# twelite_module.net
KiCad netlist of a schematic drawn in EAGLE
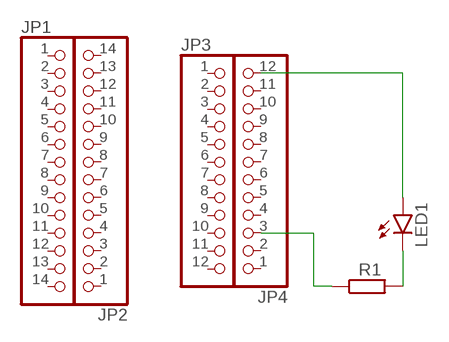
[diagram p0: schematic, sheet 1]

(export (version "E")
  (design (tool "Eeschema 10.0.6"))
  (components
    (comp (ref "JP1")
      (value "PINHD-1X14")
      (footprint "eagle-import:1X14")
      (libsource (lib "eagle-import") (part "PINHD-1X14"))
    )
    (comp (ref "JP2")
      (value "PINHD-1X14")
      (footprint "eagle-import:1X14")
      (libsource (lib "eagle-import") (part "PINHD-1X14"))
    )
    (comp (ref "JP3")
      (value "PINHD-1X12")
      (footprint "eagle-import:1X12")
      (libsource (lib "eagle-import") (part "PINHD-1X12"))
    )
    (comp (ref "JP4")
      (value "PINHD-1X12")
      (footprint "eagle-import:1X12")
      (libsource (lib "eagle-import") (part "PINHD-1X12"))
    )
    (comp (ref "LED1")
      (value "LED5MM")
      (footprint "eagle-import:LED5MM")
      (libsource (lib "eagle-import") (part "LED5MM"))
    )
    (comp (ref "R1")
      (value "R-EU_0204/7")
      (footprint "eagle-import:0204_7")
      (libsource (lib "eagle-import") (part "R-EU_0204/7"))
    )
  )
  (nets
    (net (code "1") (name "Net-(JP4-Pad3)") (class "Default")
      (node (ref "JP4") (pin "3") (pinfunction "3_3") (pintype "passive"))
      (node (ref "R1") (pin "1") (pinfunction "1_1") (pintype "passive"))
    )
    (net (code "2") (name "Net-(JP4-Pad12)") (class "Default")
      (node (ref "JP4") (pin "12") (pinfunction "12_12") (pintype "passive"))
      (node (ref "LED1") (pin "A") (pinfunction "A_A") (pintype "passive"))
    )
    (net (code "3") (name "Net-(LED1-C)") (class "Default")
      (node (ref "LED1") (pin "K") (pinfunction "C_K") (pintype "passive"))
      (node (ref "R1") (pin "2") (pinfunction "2_2") (pintype "passive"))
    )
    (net (code "4") (name "unconnected-(JP1-Pad1)") (class "Default")
      (node (ref "JP1") (pin "1") (pinfunction "1_1") (pintype "passive"))
    )
    (net (code "5") (name "unconnected-(JP1-Pad2)") (class "Default")
      (node (ref "JP1") (pin "2") (pinfunction "2_2") (pintype "passive"))
    )
    (net (code "6") (name "unconnected-(JP1-Pad3)") (class "Default")
      (node (ref "JP1") (pin "3") (pinfunction "3_3") (pintype "passive"))
    )
    (net (code "7") (name "unconnected-(JP1-Pad4)") (class "Default")
      (node (ref "JP1") (pin "4") (pinfunction "4_4") (pintype "passive"))
    )
    (net (code "8") (name "unconnected-(JP1-Pad5)") (class "Default")
      (node (ref "JP1") (pin "5") (pinfunction "5_5") (pintype "passive"))
    )
    (net (code "9") (name "unconnected-(JP1-Pad6)") (class "Default")
      (node (ref "JP1") (pin "6") (pinfunction "6_6") (pintype "passive"))
    )
    (net (code "10") (name "unconnected-(JP1-Pad7)") (class "Default")
      (node (ref "JP1") (pin "7") (pinfunction "7_7") (pintype "passive"))
    )
    (net (code "11") (name "unconnected-(JP1-Pad8)") (class "Default")
      (node (ref "JP1") (pin "8") (pinfunction "8_8") (pintype "passive"))
    )
    (net (code "12") (name "unconnected-(JP1-Pad9)") (class "Default")
      (node (ref "JP1") (pin "9") (pinfunction "9_9") (pintype "passive"))
    )
    (net (code "13") (name "unconnected-(JP1-Pad10)") (class "Default")
      (node (ref "JP1") (pin "10") (pinfunction "10_10") (pintype "passive"))
    )
    (net (code "14") (name "unconnected-(JP1-Pad11)") (class "Default")
      (node (ref "JP1") (pin "11") (pinfunction "11_11") (pintype "passive"))
    )
    (net (code "15") (name "unconnected-(JP1-Pad12)") (class "Default")
      (node (ref "JP1") (pin "12") (pinfunction "12_12") (pintype "passive"))
    )
    (net (code "16") (name "unconnected-(JP1-Pad13)") (class "Default")
      (node (ref "JP1") (pin "13") (pinfunction "13_13") (pintype "passive"))
    )
    (net (code "17") (name "unconnected-(JP1-Pad14)") (class "Default")
      (node (ref "JP1") (pin "14") (pinfunction "14_14") (pintype "passive"))
    )
    (net (code "18") (name "unconnected-(JP2-Pad1)") (class "Default")
      (node (ref "JP2") (pin "1") (pinfunction "1_1") (pintype "passive"))
    )
    (net (code "19") (name "unconnected-(JP2-Pad2)") (class "Default")
      (node (ref "JP2") (pin "2") (pinfunction "2_2") (pintype "passive"))
    )
    (net (code "20") (name "unconnected-(JP2-Pad3)") (class "Default")
      (node (ref "JP2") (pin "3") (pinfunction "3_3") (pintype "passive"))
    )
    (net (code "21") (name "unconnected-(JP2-Pad4)") (class "Default")
      (node (ref "JP2") (pin "4") (pinfunction "4_4") (pintype "passive"))
    )
    (net (code "22") (name "unconnected-(JP2-Pad5)") (class "Default")
      (node (ref "JP2") (pin "5") (pinfunction "5_5") (pintype "passive"))
    )
    (net (code "23") (name "unconnected-(JP2-Pad6)") (class "Default")
      (node (ref "JP2") (pin "6") (pinfunction "6_6") (pintype "passive"))
    )
    (net (code "24") (name "unconnected-(JP2-Pad7)") (class "Default")
      (node (ref "JP2") (pin "7") (pinfunction "7_7") (pintype "passive"))
    )
    (net (code "25") (name "unconnected-(JP2-Pad8)") (class "Default")
      (node (ref "JP2") (pin "8") (pinfunction "8_8") (pintype "passive"))
    )
    (net (code "26") (name "unconnected-(JP2-Pad9)") (class "Default")
      (node (ref "JP2") (pin "9") (pinfunction "9_9") (pintype "passive"))
    )
    (net (code "27") (name "unconnected-(JP2-Pad10)") (class "Default")
      (node (ref "JP2") (pin "10") (pinfunction "10_10") (pintype "passive"))
    )
    (net (code "28") (name "unconnected-(JP2-Pad11)") (class "Default")
      (node (ref "JP2") (pin "11") (pinfunction "11_11") (pintype "passive"))
    )
    (net (code "29") (name "unconnected-(JP2-Pad12)") (class "Default")
      (node (ref "JP2") (pin "12") (pinfunction "12_12") (pintype "passive"))
    )
    (net (code "30") (name "unconnected-(JP2-Pad13)") (class "Default")
      (node (ref "JP2") (pin "13") (pinfunction "13_13") (pintype "passive"))
    )
    (net (code "31") (name "unconnected-(JP2-Pad14)") (class "Default")
      (node (ref "JP2") (pin "14") (pinfunction "14_14") (pintype "passive"))
    )
    (net (code "32") (name "unconnected-(JP3-Pad1)") (class "Default")
      (node (ref "JP3") (pin "1") (pinfunction "1_1") (pintype "passive"))
    )
    (net (code "33") (name "unconnected-(JP3-Pad2)") (class "Default")
      (node (ref "JP3") (pin "2") (pinfunction "2_2") (pintype "passive"))
    )
    (net (code "34") (name "unconnected-(JP3-Pad3)") (class "Default")
      (node (ref "JP3") (pin "3") (pinfunction "3_3") (pintype "passive"))
    )
    (net (code "35") (name "unconnected-(JP3-Pad4)") (class "Default")
      (node (ref "JP3") (pin "4") (pinfunction "4_4") (pintype "passive"))
    )
    (net (code "36") (name "unconnected-(JP3-Pad5)") (class "Default")
      (node (ref "JP3") (pin "5") (pinfunction "5_5") (pintype "passive"))
    )
    (net (code "37") (name "unconnected-(JP3-Pad6)") (class "Default")
      (node (ref "JP3") (pin "6") (pinfunction "6_6") (pintype "passive"))
    )
    (net (code "38") (name "unconnected-(JP3-Pad7)") (class "Default")
      (node (ref "JP3") (pin "7") (pinfunction "7_7") (pintype "passive"))
    )
    (net (code "39") (name "unconnected-(JP3-Pad8)") (class "Default")
      (node (ref "JP3") (pin "8") (pinfunction "8_8") (pintype "passive"))
    )
    (net (code "40") (name "unconnected-(JP3-Pad9)") (class "Default")
      (node (ref "JP3") (pin "9") (pinfunction "9_9") (pintype "passive"))
    )
    (net (code "41") (name "unconnected-(JP3-Pad10)") (class "Default")
      (node (ref "JP3") (pin "10") (pinfunction "10_10") (pintype "passive"))
    )
    (net (code "42") (name "unconnected-(JP3-Pad11)") (class "Default")
      (node (ref "JP3") (pin "11") (pinfunction "11_11") (pintype "passive"))
    )
    (net (code "43") (name "unconnected-(JP3-Pad12)") (class "Default")
      (node (ref "JP3") (pin "12") (pinfunction "12_12") (pintype "passive"))
    )
    (net (code "44") (name "unconnected-(JP4-Pad1)") (class "Default")
      (node (ref "JP4") (pin "1") (pinfunction "1_1") (pintype "passive"))
    )
    (net (code "45") (name "unconnected-(JP4-Pad2)") (class "Default")
      (node (ref "JP4") (pin "2") (pinfunction "2_2") (pintype "passive"))
    )
    (net (code "46") (name "unconnected-(JP4-Pad4)") (class "Default")
      (node (ref "JP4") (pin "4") (pinfunction "4_4") (pintype "passive"))
    )
    (net (code "47") (name "unconnected-(JP4-Pad5)") (class "Default")
      (node (ref "JP4") (pin "5") (pinfunction "5_5") (pintype "passive"))
    )
    (net (code "48") (name "unconnected-(JP4-Pad6)") (class "Default")
      (node (ref "JP4") (pin "6") (pinfunction "6_6") (pintype "passive"))
    )
    (net (code "49") (name "unconnected-(JP4-Pad7)") (class "Default")
      (node (ref "JP4") (pin "7") (pinfunction "7_7") (pintype "passive"))
    )
    (net (code "50") (name "unconnected-(JP4-Pad8)") (class "Default")
      (node (ref "JP4") (pin "8") (pinfunction "8_8") (pintype "passive"))
    )
    (net (code "51") (name "unconnected-(JP4-Pad9)") (class "Default")
      (node (ref "JP4") (pin "9") (pinfunction "9_9") (pintype "passive"))
    )
    (net (code "52") (name "unconnected-(JP4-Pad10)") (class "Default")
      (node (ref "JP4") (pin "10") (pinfunction "10_10") (pintype "passive"))
    )
    (net (code "53") (name "unconnected-(JP4-Pad11)") (class "Default")
      (node (ref "JP4") (pin "11") (pinfunction "11_11") (pintype "passive"))
    )
  )
)
